# LittleButtons.net
KiCad netlist of a schematic drawn in Altium Designer
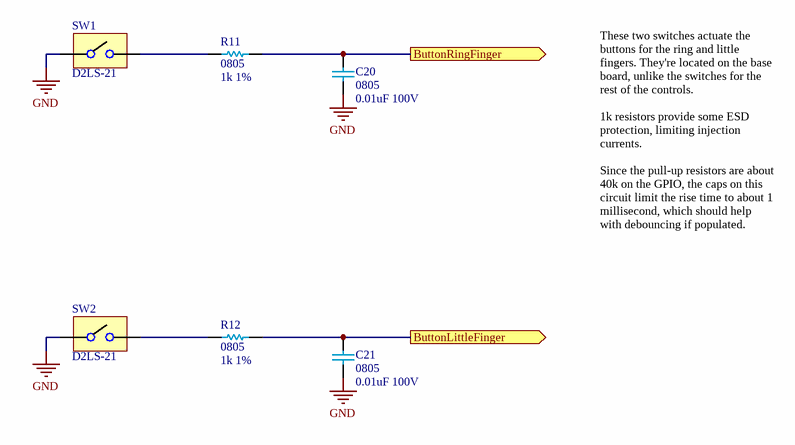
[diagram p0: LittleButtons.SchDoc]

(export (version "E")
  (design (tool "Eeschema 10.0.6"))
  (components
    (comp (ref "C20")
      (value "0805")
      (footprint "0805")
      (description "0805, X5R or better")
      (fields (field (name "ALTIUM_VALUE") "0.01uF 100V"))
      (libsource (lib "Chip_Passives") (part "Cap 0.01uF 100V"))
    )
    (comp (ref "C21")
      (value "0805")
      (footprint "0805")
      (description "0805, X5R or better")
      (fields (field (name "ALTIUM_VALUE") "0.01uF 100V"))
      (libsource (lib "Chip_Passives") (part "Cap 0.01uF 100V"))
    )
    (comp (ref "R11")
      (value "0805")
      (footprint "0805")
      (description "Chip resistor, 1/8W 100PPM")
      (fields (field (name "ALTIUM_VALUE") "1k 1%"))
      (libsource (lib "Chip_Passives") (part "Res 1k 1% 0805"))
    )
    (comp (ref "R12")
      (value "0805")
      (footprint "0805")
      (description "Chip resistor, 1/8W 100PPM")
      (fields (field (name "ALTIUM_VALUE") "1k 1%"))
      (libsource (lib "Chip_Passives") (part "Res 1k 1% 0805"))
    )
    (comp (ref "SW1")
      (value "D2LS-21")
      (footprint "D2LS-21")
      (description "Compact Surface-mounting Switch for long durability")
      (libsource (lib "Switches") (part "D2LS-21"))
    )
    (comp (ref "SW2")
      (value "D2LS-21")
      (footprint "D2LS-21")
      (description "Compact Surface-mounting Switch for long durability")
      (libsource (lib "Switches") (part "D2LS-21"))
    )
  )
  (nets
    (net (code "1") (name "/ButtonLittleFinger") (class "Default")
      (node (ref "C21") (pin "2") (pinfunction "2_2") (pintype "passive"))
      (node (ref "R12") (pin "2") (pinfunction "2_2") (pintype "passive"))
    )
    (net (code "2") (name "/ButtonRingFinger") (class "Default")
      (node (ref "C20") (pin "2") (pinfunction "2_2") (pintype "passive"))
      (node (ref "R11") (pin "2") (pinfunction "2_2") (pintype "passive"))
    )
    (net (code "3") (name "GND") (class "Default")
      (node (ref "C20") (pin "1") (pinfunction "1_1") (pintype "passive"))
      (node (ref "C21") (pin "1") (pinfunction "1_1") (pintype "passive"))
      (node (ref "SW1") (pin "A") (pinfunction "A_A") (pintype "passive"))
      (node (ref "SW2") (pin "A") (pinfunction "A_A") (pintype "passive"))
    )
    (net (code "4") (name "Net-(R11-Pad1)") (class "Default")
      (node (ref "R11") (pin "1") (pinfunction "1_1") (pintype "passive"))
      (node (ref "SW1") (pin "B") (pinfunction "B_B") (pintype "passive"))
    )
    (net (code "5") (name "Net-(R12-Pad1)") (class "Default")
      (node (ref "R12") (pin "1") (pinfunction "1_1") (pintype "passive"))
      (node (ref "SW2") (pin "B") (pinfunction "B_B") (pintype "passive"))
    )
  )
)
